# Control.net
KiCad netlist of a schematic drawn in Altium Designer
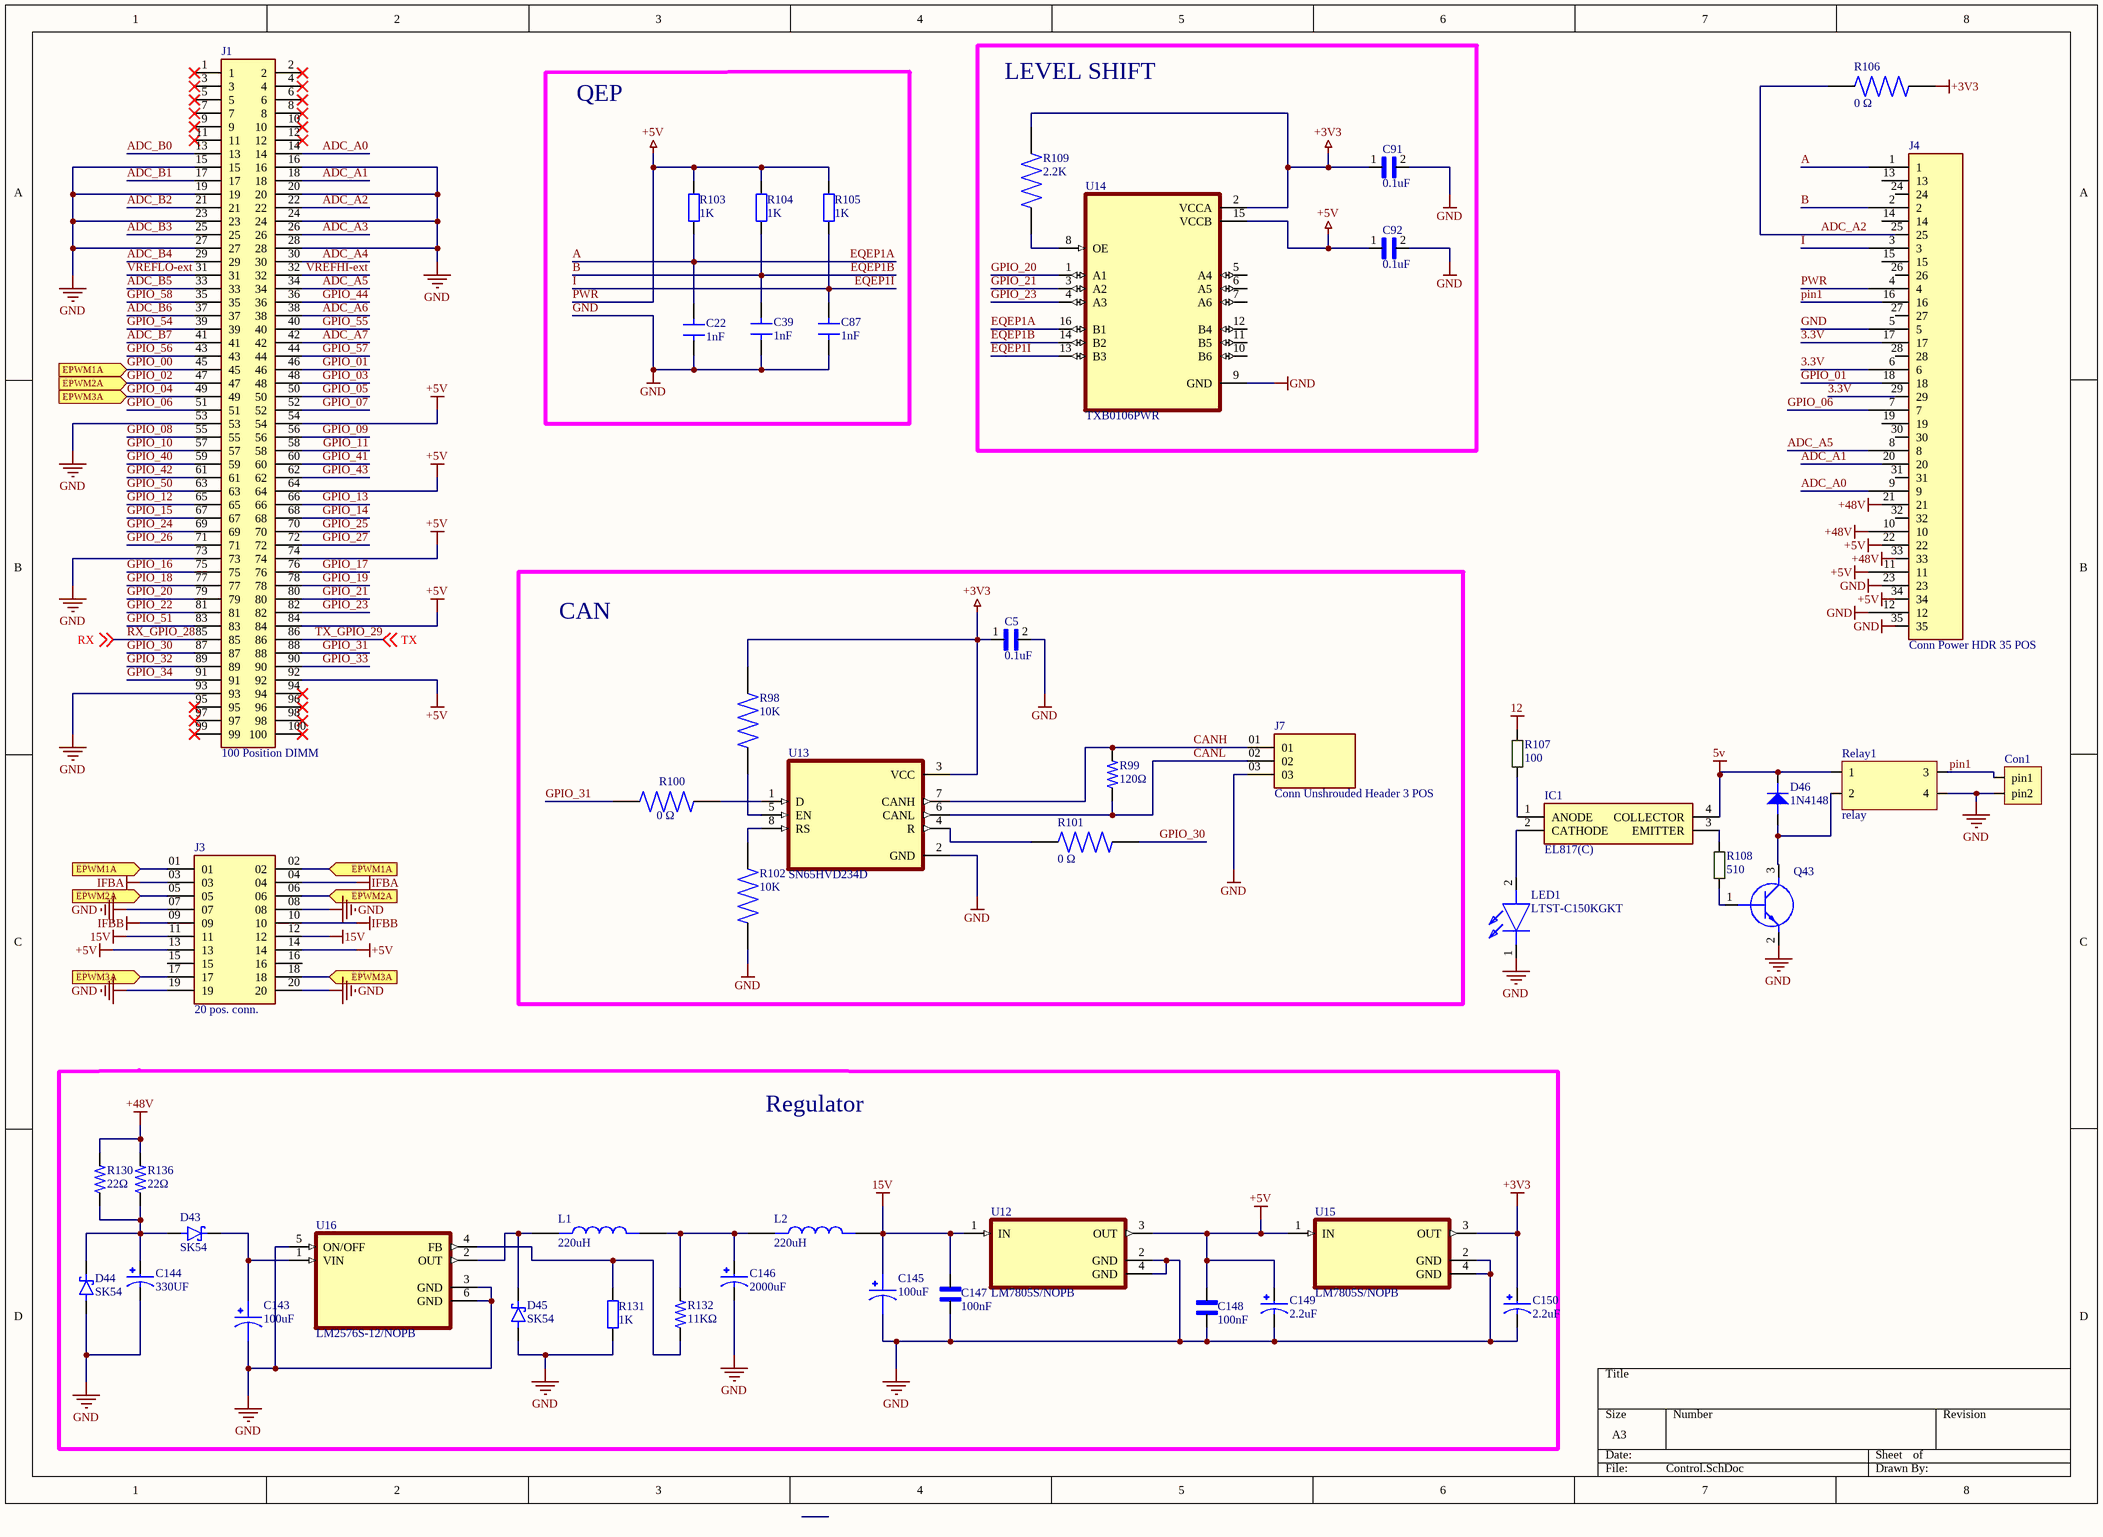
[diagram p0: Control.SchDoc]

(export (version "E")
  (design (tool "Eeschema 10.0.6"))
  (components
    (comp (ref "C5")
      (value "0.1uF")
      (footprint "CAPC2012X88N")
      (description "Cap Ceramic 0.1uF 35V X7R 10% SMD 0805 125Â°C Paper T/R")
      (fields (field (name "MP") "C0805C104K6RACTU") (field (name "MF") "KEMET"))
      (libsource (lib "PROJE") (part "CAP 0.1uF SMD 0805"))
    )
    (comp (ref "C22")
      (value "1nF")
      (footprint "CAP 1206_3216 - 1.8MM")
      (libsource (lib "PROJE") (part "CAP 1nF 1206"))
    )
    (comp (ref "C39")
      (value "1nF")
      (footprint "CAP 1206_3216 - 1.8MM")
      (libsource (lib "PROJE") (part "CAP 1nF 1206"))
    )
    (comp (ref "C87")
      (value "1nF")
      (footprint "CAP 1206_3216 - 1.8MM")
      (libsource (lib "PROJE") (part "CAP 1nF 1206"))
    )
    (comp (ref "C91")
      (value "0.1uF")
      (footprint "CAPC2012X88N")
      (description "Cap Ceramic 0.1uF 35V X7R 10% SMD 0805 125Â°C Paper T/R")
      (fields (field (name "MP") "C0805C104K6RACTU") (field (name "MF") "KEMET"))
      (libsource (lib "PROJE") (part "CAP 0.1uF SMD 0805"))
    )
    (comp (ref "C92")
      (value "0.1uF")
      (footprint "CAPC2012X88N")
      (description "Cap Ceramic 0.1uF 35V X7R 10% SMD 0805 125Â°C Paper T/R")
      (fields (field (name "MP") "C0805C104K6RACTU") (field (name "MF") "KEMET"))
      (libsource (lib "PROJE") (part "CAP 0.1uF SMD 0805"))
    )
    (comp (ref "C143")
      (value "100uF")
      (footprint "CapSmdElc")
      (libsource (lib "PROJE") (part "100 uF Electr Cap"))
    )
    (comp (ref "C144")
      (value "330UF")
      (footprint "CAP_EEETC1C331V")
      (description "CAP ALUM 330UF 20% 16V SMD")
      (fields (field (name "MP") "EEE-TC1C331V") (field (name "MF") "Panasonic Electronic Components"))
      (libsource (lib "PROJE") (part "CAP 330UF SMD"))
    )
    (comp (ref "C145")
      (value "100uF")
      (footprint "CapSmdElc")
      (libsource (lib "PROJE") (part "100 uF Electr Cap"))
    )
    (comp (ref "C146")
      (value "2000uF")
      (footprint "CAPPRD500W60D1000H1600")
      (description "CAP ALUM 2000UF 20% 6.3V RADIAL - Electrolytic")
      (fields (field (name "MP") "EEUFS0J202") (field (name "MF") "Panasonic"))
      (libsource (lib "PROJE") (part "2000uF"))
    )
    (comp (ref "C147")
      (value "100nF")
      (footprint "C-0805W")
      (fields
        (field (name "MF") "Wurth Electronics Inc")
        (field (name "MP") "885012207098")
        (field (name "BUYPART") "https://www.snapeda.com/parts/885012207098/Wurth%20Electronics%20Inc/view-part/4217223/?ref=eda")
      )
      (libsource (lib "PROJE") (part "CAP 100nF 50V SMT 0805"))
    )
    (comp (ref "C148")
      (value "100nF")
      (footprint "C-0805W")
      (fields
        (field (name "MF") "Wurth Electronics Inc")
        (field (name "MP") "885012207098")
        (field (name "BUYPART") "https://www.snapeda.com/parts/885012207098/Wurth%20Electronics%20Inc/view-part/4217223/?ref=eda")
      )
      (libsource (lib "PROJE") (part "CAP 100nF 50V SMT 0805"))
    )
    (comp (ref "C149")
      (value "2.2uF")
      (footprint "CapSmdElc")
      (description "Electrolytic Capacitor")
      (libsource (lib "PROJE") (part "CAP 2.2uF"))
    )
    (comp (ref "C150")
      (value "2.2uF")
      (footprint "CapSmdElc")
      (description "Electrolytic Capacitor")
      (libsource (lib "PROJE") (part "CAP 2.2uF"))
    )
    (comp (ref "Con1")
      (value "2pinConnector")
      (footprint "2pinCon")
      (description "CON.T.B.2.54MM 2P 180C MALE IVORY CONNFLY")
      (fields (field (name "ÖZDISAN PART NUMBER") "DS1070-2MVV6") (field (name "MANUFACTURER") "CONNFLY"))
      (libsource (lib "Mobile Charger") (part "2pinConnector"))
    )
    (comp (ref "D43")
      (value "SK54")
      (footprint "DIOM7959X265N")
      (description "Diode Schottky 40V 5A Surface Mount DO-214AA (SMB)")
      (fields (field (name "MP") "MBRS320T3G") (field (name "MF") "ON Semiconductor"))
      (libsource (lib "PROJE") (part "SK54"))
    )
    (comp (ref "D44")
      (value "SK54")
      (footprint "DIOM7959X265N")
      (description "Diode Schottky 40V 5A Surface Mount DO-214AA (SMB)")
      (fields (field (name "MP") "MBRS320T3G") (field (name "MF") "ON Semiconductor"))
      (libsource (lib "PROJE") (part "SK54"))
    )
    (comp (ref "D45")
      (value "SK54")
      (footprint "DIOM7959X265N")
      (description "Diode Schottky 40V 5A Surface Mount DO-214AA (SMB)")
      (fields (field (name "MP") "MBRS320T3G") (field (name "MF") "ON Semiconductor"))
      (libsource (lib "PROJE") (part "SK54"))
    )
    (comp (ref "D46")
      (value "1N4148")
      (footprint "SOD-123")
      (description "DIODE FAST SWITCHING Single 150mA 75V SMT SOD323")
      (fields (field (name "ÖZDISAN PART NUMBER") "1N4148WS-HT") (field (name "MANUFACTURER") "HOTTECH"))
      (libsource (lib "Mobile Charger") (part "1N4148"))
    )
    (comp (ref "IC1")
      (value "EL817(C)")
      (footprint "DIP762W60P254L458H480Q4N")
      (description "IC-817 OPTOC.TRANS.OUTPUT DIP4")
      (fields (field (name "ÖZDISAN PART NUMBER") "PC817B=PC817X2NSZW") (field (name "MANUFACTURER") "SHARP"))
      (libsource (lib "Mobile Charger") (part "EL817(C)"))
    )
    (comp (ref "J1")
      (value "100 Position DIMM")
      (footprint "TE_5390213-1")
      (description "100 Position DIMM DRAM Socket Through Hole")
      (fields (field (name "MP") "5390213-1") (field (name "MF") "TE Connectivity"))
      (libsource (lib "PROJE") (part "100 Position DIMM"))
    )
    (comp (ref "J3")
      (value "20 pos. conn.")
      (footprint "SAMTEC_SSQ-110-X-X-D")
      (description "SSQ - Samtec 2.54mm Square Tail Dual Row Socket Strip 8.5mm Profile - Fast Stock")
      (fields (field (name "MF") "Samtec") (field (name "MP") "SSQ-110-23-G-D"))
      (libsource (lib "PROJE") (part "20 pos. conn."))
    )
    (comp (ref "J4")
      (value "Conn Power HDR 35 POS")
      (footprint "TE_776230-2")
      (description "Conn Power HDR 35 POS 4mm Solder ST Thru-Hole 35 Terminal 1 Port Automotive Loose")
      (fields (field (name "MP") "776230-2") (field (name "MF") "TE Connectivity"))
      (libsource (lib "PROJE") (part "Conn Power HDR 35 POS"))
    )
    (comp (ref "J7")
      (value "Conn Unshrouded Header 3 POS")
      (footprint "SAMTEC_TSW-103-17-S-S")
      (fields (field (name "MP") "TSW-103-17-S-S"))
      (libsource (lib "PROJE") (part "Conn Unshrouded Header 3 POS"))
    )
    (comp (ref "L1")
      (value "220uH")
      (footprint "IND_MDH12577C-101MA=P3")
      (description "Inductor Power Shielded Wirewound 220uH 20% 100KHz Ferrite 1.1A 0.325Ohm DCR 5049 Automotive T/R")
      (fields (field (name "MP") "MDH12577C-101MA=P3"))
      (libsource (lib "PROJE") (part "220uH Inductor SMD"))
    )
    (comp (ref "L2")
      (value "220uH")
      (footprint "IND_MDH12577C-101MA=P3")
      (description "Inductor Power Shielded Wirewound 220uH 20% 100KHz Ferrite 1.1A 0.325Ohm DCR 5049 Automotive T/R")
      (fields (field (name "MP") "MDH12577C-101MA=P3"))
      (libsource (lib "PROJE") (part "220uH Inductor SMD"))
    )
    (comp (ref "LED1")
      (value "LTST-C150KGKT")
      (footprint "L-1206")
      (description "LED SMD 1206 GREEN WATER CLEAR 18~71 mcd")
      (fields (field (name "MANUFACTURER") "LITEON"))
      (libsource (lib "Mobile Charger") (part "LTST-C150KGKT"))
    )
    (comp (ref "Q43")
      (value "BC817-40,235")
      (footprint "SamacSys:SOT95P230X110-3N")
      (description "TRANSISTOR DIS.500mA 45V NPN SOT23 GEN. SMT")
      (fields (field (name "MANUFACTURER") "NXP (PHILIPS)"))
      (libsource (lib "*") (part "BC817-40,235"))
    )
    (comp (ref "R98")
      (value "10K")
      (footprint "RESC2012X70N")
      (description "Precision Thick Film Surface Mnt Resistor 0805 10kOhm +/-0.5% 0.1W +/-50ppm/degC")
      (fields (field (name "MP") "ERJ6RBD1002V") (field (name "MF") "Panasonic"))
      (libsource (lib "PROJE") (part "RES 10K 0805"))
    )
    (comp (ref "R99")
      (value "120Ω")
      (footprint "RESC2012X65N")
      (description "RESISTOR, THICK FILM, 120R, 5%, 0805")
      (fields (field (name "MP") "CRGS0805J120R"))
      (libsource (lib "PROJE") (part "RES 120Ω 0805"))
    )
    (comp (ref "R100")
      (value "0 Ω")
      (footprint "RES 0.0 OHM 1206")
      (libsource (lib "PROJE") (part "RES 0.0 Ω 1206"))
    )
    (comp (ref "R101")
      (value "0 Ω")
      (footprint "RES 0.0 OHM 1206")
      (libsource (lib "PROJE") (part "RES 0.0 Ω 1206"))
    )
    (comp (ref "R102")
      (value "10K")
      (footprint "RESC2012X70N")
      (description "Precision Thick Film Surface Mnt Resistor 0805 10kOhm +/-0.5% 0.1W +/-50ppm/degC")
      (fields (field (name "MP") "ERJ6RBD1002V") (field (name "MF") "Panasonic"))
      (libsource (lib "PROJE") (part "RES 10K 0805"))
    )
    (comp (ref "R103")
      (value "RES SMD 1K OHM 1% 1/8W 0805")
      (footprint "RES_0805")
      (description "1 kOhms ±1% 0.125W, 1/8W Chip Resistor 0805 (2012 Metric) Moisture Resistant Thick Film")
      (fields (field (name "DEGER") "1K"))
      (libsource (lib "PROJE") (part "1K 0805"))
    )
    (comp (ref "R104")
      (value "RES SMD 1K OHM 1% 1/8W 0805")
      (footprint "RES_0805")
      (description "1 kOhms ±1% 0.125W, 1/8W Chip Resistor 0805 (2012 Metric) Moisture Resistant Thick Film")
      (fields (field (name "DEGER") "1K"))
      (libsource (lib "PROJE") (part "1K 0805"))
    )
    (comp (ref "R105")
      (value "RES SMD 1K OHM 1% 1/8W 0805")
      (footprint "RES_0805")
      (description "1 kOhms ±1% 0.125W, 1/8W Chip Resistor 0805 (2012 Metric) Moisture Resistant Thick Film")
      (fields (field (name "DEGER") "1K"))
      (libsource (lib "PROJE") (part "1K 0805"))
    )
    (comp (ref "R106")
      (value "0 Ω")
      (footprint "RES 0.0 OHM 1206")
      (libsource (lib "PROJE") (part "RES 0.0 Ω 1206"))
    )
    (comp (ref "R107")
      (value "100")
      (footprint "R-1206")
      (description "RES.(3216) 1206 100 Ohms 5% 1/4W 100PPM")
      (fields (field (name "ÖZDISAN PART NUMBER") "RC3216J101CS") (field (name "MANUFACTURER") "SAMSUNG"))
      (libsource (lib "Mobile Charger") (part "R-1206"))
    )
    (comp (ref "R108")
      (value "510")
      (footprint "R-1206")
      (description "RES.(3216) 1206 510 Ohms 1% 1/4W-S 100PPM")
      (fields (field (name "ÖZDISAN PART NUMBER") "1206S4F5100T5E") (field (name "MANUFACTURER") "ROYALOHM"))
      (libsource (lib "Mobile Charger") (part "R-1206"))
    )
    (comp (ref "R109")
      (value "2.2K")
      (footprint "RESC3115X65N-2.2K-1206")
      (description "RES SMD 2.2K OHM 1% 1/4W 1206")
      (fields (field (name "MP") "CRG1206F2K2/10"))
      (libsource (lib "PROJE") (part "RES 2.2K 1206"))
    )
    (comp (ref "R130") (value "22Ω") (footprint "R-2512R") (libsource (lib "PROJE") (part "RES 22Ω 2512")))
    (comp (ref "R131")
      (value "RES SMD 1K OHM 1% 1/8W 0805")
      (footprint "RES_0805")
      (description "1 kOhms ±1% 0.125W, 1/8W Chip Resistor 0805 (2012 Metric) Moisture Resistant Thick Film")
      (fields (field (name "DEGER") "1K"))
      (libsource (lib "PROJE") (part "1K 0805"))
    )
    (comp (ref "R132")
      (value "11KΩ")
      (footprint "RESC2012X50N")
      (description "THICK FILM RESISTOR, 11KOHM, 125mW, 5%")
      (fields (field (name "MP") "CRCW080511K0JNEA"))
      (libsource (lib "PROJE") (part "RES 11KΩ SMD"))
    )
    (comp (ref "R136") (value "22Ω") (footprint "R-2512R") (libsource (lib "PROJE") (part "RES 22Ω 2512")))
    (comp (ref "Relay1")
      (value "relay")
      (footprint "Relay")
      (description "RELAY 3A 5VDC 1a PANASONIC")
      (fields (field (name "ÖZDISAN PART NUMBER") "ALJ105W") (field (name "MANUFACTURER") "PANASONIC COMP."))
      (libsource (lib "Mobile Charger") (part "relay"))
    )
    (comp (ref "U12")
      (value "LM7805S/NOPB")
      (footprint "TO254P1524X483-4N")
      (description "1.5-A, 30-V, linear voltage regulator 3-DDPAK/TO-263 0 to 125")
      (fields (field (name "MF") "Texas Instruments"))
      (libsource (lib "PROJE") (part "LM7805S/NOPB"))
    )
    (comp (ref "U13")
      (value "SN65HVD234D")
      (footprint "SOIC127P599X175-8N")
      (description "3.3 V CAN Transceiver with Sleep Mode 8-SOIC -40 to 125")
      (fields (field (name "MF") "Texas Instruments"))
      (libsource (lib "PROJE") (part "SN65HVD234D"))
    )
    (comp (ref "U14")
      (value "TXB0106PWR")
      (footprint "SOP65P640X120-16N")
      (fields
        (field (name "MF") "Texas Instruments")
        (field (name "BUYPART") "https://www.snapeda.com/parts/TXB0106PWR/Texas%20Instruments/view-part/134340/?ref=eda")
      )
      (libsource (lib "PROJE") (part "TXB0106PWR"))
    )
    (comp (ref "U15")
      (value "LM7805S/NOPB")
      (footprint "TO254P1524X483-4N")
      (description "1.5-A, 30-V, linear voltage regulator 3-DDPAK/TO-263 0 to 125")
      (fields (field (name "MF") "Texas Instruments"))
      (libsource (lib "PROJE") (part "LM7805S/NOPB"))
    )
    (comp (ref "U16")
      (value "LM2576S-12/NOPB")
      (footprint "VREG_TPS79625KTTR")
      (description "SIMPLE SWITCHER&reg; 40V, 3A Low Component Count Step-Down Regulator 5-DDPAK/TO-263 -40 to 125")
      (fields
        (field (name "MF") "Texas Instruments")
        (field (name "BUYPART") "https://www.snapeda.com/parts/LM2576S-12/NOPB/Texas%20Instruments/view-part/470772/?ref=eda")
      )
      (libsource (lib "PROJE") (part "LM2576S-12/NOPB"))
    )
  )
  (nets
    (net (code "1") (name "+3V3") (class "Default")
      (node (ref "C150") (pin "1") (pinfunction "1_1") (pintype "passive"))
      (node (ref "C5") (pin "1") (pinfunction "1_1") (pintype "passive"))
      (node (ref "C91") (pin "1") (pinfunction "1_1") (pintype "passive"))
      (node (ref "R106") (pin "1") (pinfunction "1_1") (pintype "passive"))
      (node (ref "R109") (pin "2") (pinfunction "2_2") (pintype "passive"))
      (node (ref "R98") (pin "2") (pinfunction "2_2") (pintype "passive"))
      (node (ref "U13") (pin "3") (pinfunction "VCC_3") (pintype "power_in"))
      (node (ref "U14") (pin "2") (pinfunction "VCCA_2") (pintype "power_in"))
      (node (ref "U15") (pin "3") (pinfunction "OUT_3") (pintype "output"))
    )
    (net (code "2") (name "+5V") (class "Default")
      (node (ref "C148") (pin "2") (pinfunction "2_2") (pintype "passive"))
      (node (ref "C149") (pin "1") (pinfunction "1_1") (pintype "passive"))
      (node (ref "C92") (pin "1") (pinfunction "1_1") (pintype "passive"))
      (node (ref "J1") (pin "54") (pinfunction "54_54") (pintype "passive"))
      (node (ref "J1") (pin "64") (pinfunction "64_64") (pintype "passive"))
      (node (ref "J1") (pin "74") (pinfunction "74_74") (pintype "passive"))
      (node (ref "J1") (pin "84") (pinfunction "84_84") (pintype "passive"))
      (node (ref "J1") (pin "92") (pinfunction "92_92") (pintype "passive"))
      (node (ref "J3") (pin "13") (pinfunction "13_13") (pintype "passive"))
      (node (ref "J3") (pin "14") (pinfunction "14_14") (pintype "passive"))
      (node (ref "J4") (pin "11") (pinfunction "11_11") (pintype "passive"))
      (node (ref "J4") (pin "22") (pinfunction "22_22") (pintype "passive"))
      (node (ref "J4") (pin "34") (pinfunction "34_34") (pintype "passive"))
      (node (ref "J4") (pin "4") (pinfunction "4_4") (pintype "passive"))
      (node (ref "R103") (pin "2") (pinfunction "2_2") (pintype "passive"))
      (node (ref "R104") (pin "2") (pinfunction "2_2") (pintype "passive"))
      (node (ref "R105") (pin "2") (pinfunction "2_2") (pintype "passive"))
      (node (ref "U12") (pin "3") (pinfunction "OUT_3") (pintype "output"))
      (node (ref "U14") (pin "15") (pinfunction "VCCB_15") (pintype "power_in"))
      (node (ref "U15") (pin "1") (pinfunction "IN_1") (pintype "input"))
    )
    (net (code "3") (name "+48V") (class "Default")
      (node (ref "J4") (pin "10") (pinfunction "10_10") (pintype "passive"))
      (node (ref "J4") (pin "21") (pinfunction "21_21") (pintype "passive"))
      (node (ref "J4") (pin "33") (pinfunction "33_33") (pintype "passive"))
      (node (ref "R130") (pin "2") (pinfunction "2_2") (pintype "passive"))
      (node (ref "R136") (pin "2") (pinfunction "2_2") (pintype "passive"))
    )
    (net (code "4") (name "/3.3V") (class "Default")
      (node (ref "J4") (pin "17") (pinfunction "17_17") (pintype "passive"))
      (node (ref "J4") (pin "29") (pinfunction "29_29") (pintype "passive"))
      (node (ref "J4") (pin "6") (pinfunction "6_6") (pintype "passive"))
    )
    (net (code "5") (name "/A") (class "Default")
      (node (ref "C22") (pin "2") (pinfunction "2_2") (pintype "passive"))
      (node (ref "J4") (pin "1") (pinfunction "1_1") (pintype "passive"))
      (node (ref "R103") (pin "1") (pinfunction "1_1") (pintype "passive"))
      (node (ref "U14") (pin "16") (pinfunction "B1_16") (pintype "bidirectional"))
    )
    (net (code "6") (name "/ADC_A0") (class "Default")
      (node (ref "J1") (pin "14") (pinfunction "14_14") (pintype "passive"))
      (node (ref "J4") (pin "9") (pinfunction "9_9") (pintype "passive"))
    )
    (net (code "7") (name "/ADC_A1") (class "Default")
      (node (ref "J1") (pin "18") (pinfunction "18_18") (pintype "passive"))
      (node (ref "J4") (pin "20") (pinfunction "20_20") (pintype "passive"))
    )
    (net (code "8") (name "/ADC_A2") (class "Default")
      (node (ref "J1") (pin "22") (pinfunction "22_22") (pintype "passive"))
      (node (ref "J4") (pin "25") (pinfunction "25_25") (pintype "passive"))
      (node (ref "R106") (pin "2") (pinfunction "2_2") (pintype "passive"))
    )
    (net (code "9") (name "/ADC_A3") (class "Default")
      (node (ref "J1") (pin "26") (pinfunction "26_26") (pintype "passive"))
    )
    (net (code "10") (name "/ADC_A4") (class "Default")
      (node (ref "J1") (pin "30") (pinfunction "30_30") (pintype "passive"))
    )
    (net (code "11") (name "/ADC_A5") (class "Default")
      (node (ref "J1") (pin "34") (pinfunction "34_34") (pintype "passive"))
      (node (ref "J4") (pin "8") (pinfunction "8_8") (pintype "passive"))
    )
    (net (code "12") (name "/ADC_A6") (class "Default")
      (node (ref "J1") (pin "38") (pinfunction "38_38") (pintype "passive"))
    )
    (net (code "13") (name "/ADC_A7") (class "Default")
      (node (ref "J1") (pin "42") (pinfunction "42_42") (pintype "passive"))
    )
    (net (code "14") (name "/ADC_B0") (class "Default")
      (node (ref "J1") (pin "13") (pinfunction "13_13") (pintype "passive"))
    )
    (net (code "15") (name "/ADC_B1") (class "Default")
      (node (ref "J1") (pin "17") (pinfunction "17_17") (pintype "passive"))
    )
    (net (code "16") (name "/ADC_B2") (class "Default")
      (node (ref "J1") (pin "21") (pinfunction "21_21") (pintype "passive"))
    )
    (net (code "17") (name "/ADC_B3") (class "Default")
      (node (ref "J1") (pin "25") (pinfunction "25_25") (pintype "passive"))
    )
    (net (code "18") (name "/ADC_B4") (class "Default")
      (node (ref "J1") (pin "29") (pinfunction "29_29") (pintype "passive"))
    )
    (net (code "19") (name "/ADC_B5") (class "Default")
      (node (ref "J1") (pin "33") (pinfunction "33_33") (pintype "passive"))
    )
    (net (code "20") (name "/ADC_B6") (class "Default")
      (node (ref "J1") (pin "37") (pinfunction "37_37") (pintype "passive"))
    )
    (net (code "21") (name "/ADC_B7") (class "Default")
      (node (ref "J1") (pin "41") (pinfunction "41_41") (pintype "passive"))
    )
    (net (code "22") (name "/B") (class "Default")
      (node (ref "C39") (pin "2") (pinfunction "2_2") (pintype "passive"))
      (node (ref "J4") (pin "2") (pinfunction "2_2") (pintype "passive"))
      (node (ref "R104") (pin "1") (pinfunction "1_1") (pintype "passive"))
      (node (ref "U14") (pin "14") (pinfunction "B2_14") (pintype "bidirectional"))
    )
    (net (code "23") (name "/CANH") (class "Default")
      (node (ref "J7") (pin "01") (pinfunction "01_01") (pintype "passive"))
      (node (ref "R99") (pin "2") (pinfunction "2_2") (pintype "passive"))
      (node (ref "U13") (pin "7") (pinfunction "CANH_7") (pintype "output"))
    )
    (net (code "24") (name "/CANL") (class "Default")
      (node (ref "J7") (pin "02") (pinfunction "02_02") (pintype "passive"))
      (node (ref "R99") (pin "1") (pinfunction "1_1") (pintype "passive"))
      (node (ref "U13") (pin "6") (pinfunction "CANL_6") (pintype "output"))
    )
    (net (code "25") (name "/EQEP1I") (class "Default")
      (node (ref "C87") (pin "2") (pinfunction "2_2") (pintype "passive"))
      (node (ref "J4") (pin "3") (pinfunction "3_3") (pintype "passive"))
      (node (ref "R105") (pin "1") (pinfunction "1_1") (pintype "passive"))
      (node (ref "U14") (pin "13") (pinfunction "B3_13") (pintype "bidirectional"))
    )
    (net (code "26") (name "/GPIO_00") (class "Default")
      (node (ref "J1") (pin "45") (pinfunction "45_45") (pintype "passive"))
      (node (ref "J3") (pin "01") (pinfunction "01_01") (pintype "passive"))
      (node (ref "J3") (pin "02") (pinfunction "02_02") (pintype "passive"))
    )
    (net (code "27") (name "/GPIO_01") (class "Default")
      (node (ref "J1") (pin "46") (pinfunction "46_46") (pintype "passive"))
      (node (ref "J4") (pin "18") (pinfunction "18_18") (pintype "passive"))
    )
    (net (code "28") (name "/GPIO_02") (class "Default")
      (node (ref "J1") (pin "47") (pinfunction "47_47") (pintype "passive"))
      (node (ref "J3") (pin "05") (pinfunction "05_05") (pintype "passive"))
      (node (ref "J3") (pin "06") (pinfunction "06_06") (pintype "passive"))
    )
    (net (code "29") (name "/GPIO_03") (class "Default")
      (node (ref "J1") (pin "48") (pinfunction "48_48") (pintype "passive"))
    )
    (net (code "30") (name "/GPIO_04") (class "Default")
      (node (ref "J1") (pin "49") (pinfunction "49_49") (pintype "passive"))
      (node (ref "J3") (pin "17") (pinfunction "17_17") (pintype "passive"))
      (node (ref "J3") (pin "18") (pinfunction "18_18") (pintype "passive"))
    )
    (net (code "31") (name "/GPIO_05") (class "Default")
      (node (ref "J1") (pin "50") (pinfunction "50_50") (pintype "passive"))
    )
    (net (code "32") (name "/GPIO_06") (class "Default")
      (node (ref "J1") (pin "51") (pinfunction "51_51") (pintype "passive"))
      (node (ref "J4") (pin "7") (pinfunction "7_7") (pintype "passive"))
    )
    (net (code "33") (name "/GPIO_07") (class "Default")
      (node (ref "J1") (pin "52") (pinfunction "52_52") (pintype "passive"))
    )
    (net (code "34") (name "/GPIO_08") (class "Default")
      (node (ref "J1") (pin "55") (pinfunction "55_55") (pintype "passive"))
    )
    (net (code "35") (name "/GPIO_09") (class "Default")
      (node (ref "J1") (pin "56") (pinfunction "56_56") (pintype "passive"))
    )
    (net (code "36") (name "/GPIO_10") (class "Default")
      (node (ref "J1") (pin "57") (pinfunction "57_57") (pintype "passive"))
    )
    (net (code "37") (name "/GPIO_11") (class "Default")
      (node (ref "J1") (pin "58") (pinfunction "58_58") (pintype "passive"))
    )
    (net (code "38") (name "/GPIO_12") (class "Default")
      (node (ref "J1") (pin "65") (pinfunction "65_65") (pintype "passive"))
    )
    (net (code "39") (name "/GPIO_13") (class "Default")
      (node (ref "J1") (pin "66") (pinfunction "66_66") (pintype "passive"))
    )
    (net (code "40") (name "/GPIO_14") (class "Default")
      (node (ref "J1") (pin "68") (pinfunction "68_68") (pintype "passive"))
    )
    (net (code "41") (name "/GPIO_15") (class "Default")
      (node (ref "J1") (pin "67") (pinfunction "67_67") (pintype "passive"))
    )
    (net (code "42") (name "/GPIO_16") (class "Default")
      (node (ref "J1") (pin "75") (pinfunction "75_75") (pintype "passive"))
    )
    (net (code "43") (name "/GPIO_17") (class "Default")
      (node (ref "J1") (pin "76") (pinfunction "76_76") (pintype "passive"))
    )
    (net (code "44") (name "/GPIO_18") (class "Default")
      (node (ref "J1") (pin "77") (pinfunction "77_77") (pintype "passive"))
    )
    (net (code "45") (name "/GPIO_19") (class "Default")
      (node (ref "J1") (pin "78") (pinfunction "78_78") (pintype "passive"))
    )
    (net (code "46") (name "/GPIO_20") (class "Default")
      (node (ref "J1") (pin "79") (pinfunction "79_79") (pintype "passive"))
      (node (ref "U14") (pin "1") (pinfunction "A1_1") (pintype "bidirectional"))
    )
    (net (code "47") (name "/GPIO_21") (class "Default")
      (node (ref "J1") (pin "80") (pinfunction "80_80") (pintype "passive"))
      (node (ref "U14") (pin "3") (pinfunction "A2_3") (pintype "bidirectional"))
    )
    (net (code "48") (name "/GPIO_22") (class "Default")
      (node (ref "J1") (pin "81") (pinfunction "81_81") (pintype "passive"))
    )
    (net (code "49") (name "/GPIO_23") (class "Default")
      (node (ref "J1") (pin "82") (pinfunction "82_82") (pintype "passive"))
      (node (ref "U14") (pin "4") (pinfunction "A3_4") (pintype "bidirectional"))
    )
    (net (code "50") (name "/GPIO_24") (class "Default")
      (node (ref "J1") (pin "69") (pinfunction "69_69") (pintype "passive"))
    )
    (net (code "51") (name "/GPIO_25") (class "Default")
      (node (ref "J1") (pin "70") (pinfunction "70_70") (pintype "passive"))
    )
    (net (code "52") (name "/GPIO_26") (class "Default")
      (node (ref "J1") (pin "71") (pinfunction "71_71") (pintype "passive"))
    )
    (net (code "53") (name "/GPIO_27") (class "Default")
      (node (ref "J1") (pin "72") (pinfunction "72_72") (pintype "passive"))
    )
    (net (code "54") (name "/GPIO_30") (class "Default")
      (node (ref "J1") (pin "87") (pinfunction "87_87") (pintype "passive"))
      (node (ref "R101") (pin "1") (pinfunction "1_1") (pintype "passive"))
    )
    (net (code "55") (name "/GPIO_31") (class "Default")
      (node (ref "J1") (pin "88") (pinfunction "88_88") (pintype "passive"))
      (node (ref "R100") (pin "1") (pinfunction "1_1") (pintype "passive"))
    )
    (net (code "56") (name "/GPIO_32") (class "Default")
      (node (ref "J1") (pin "89") (pinfunction "89_89") (pintype "passive"))
    )
    (net (code "57") (name "/GPIO_33") (class "Default")
      (node (ref "J1") (pin "90") (pinfunction "90_90") (pintype "passive"))
    )
    (net (code "58") (name "/GPIO_34") (class "Default")
      (node (ref "J1") (pin "91") (pinfunction "91_91") (pintype "passive"))
    )
    (net (code "59") (name "/GPIO_40") (class "Default")
      (node (ref "J1") (pin "59") (pinfunction "59_59") (pintype "passive"))
    )
    (net (code "60") (name "/GPIO_41") (class "Default")
      (node (ref "J1") (pin "60") (pinfunction "60_60") (pintype "passive"))
    )
    (net (code "61") (name "/GPIO_42") (class "Default")
      (node (ref "J1") (pin "61") (pinfunction "61_61") (pintype "passive"))
    )
    (net (code "62") (name "/GPIO_43") (class "Default")
      (node (ref "J1") (pin "62") (pinfunction "62_62") (pintype "passive"))
    )
    (net (code "63") (name "/GPIO_44") (class "Default")
      (node (ref "J1") (pin "36") (pinfunction "36_36") (pintype "passive"))
    )
    (net (code "64") (name "/GPIO_50") (class "Default")
      (node (ref "J1") (pin "63") (pinfunction "63_63") (pintype "passive"))
    )
    (net (code "65") (name "/GPIO_51") (class "Default")
      (node (ref "J1") (pin "83") (pinfunction "83_83") (pintype "passive"))
    )
    (net (code "66") (name "/GPIO_54") (class "Default")
      (node (ref "J1") (pin "39") (pinfunction "39_39") (pintype "passive"))
    )
    (net (code "67") (name "/GPIO_55") (class "Default")
      (node (ref "J1") (pin "40") (pinfunction "40_40") (pintype "passive"))
    )
    (net (code "68") (name "/GPIO_56") (class "Default")
      (node (ref "J1") (pin "43") (pinfunction "43_43") (pintype "passive"))
    )
    (net (code "69") (name "/GPIO_57") (class "Default")
      (node (ref "J1") (pin "44") (pinfunction "44_44") (pintype "passive"))
    )
    (net (code "70") (name "/GPIO_58") (class "Default")
      (node (ref "J1") (pin "35") (pinfunction "35_35") (pintype "passive"))
    )
    (net (code "71") (name "/VREFHI-ext") (class "Default")
      (node (ref "J1") (pin "32") (pinfunction "32_32") (pintype "passive"))
    )
    (net (code "72") (name "/VREFLO-ext") (class "Default")
      (node (ref "J1") (pin "31") (pinfunction "31_31") (pintype "passive"))
    )
    (net (code "73") (name "/pin1") (class "Default")
      (node (ref "Con1") (pin "1") (pinfunction "pin1_1") (pintype "passive"))
      (node (ref "J4") (pin "16") (pinfunction "16_16") (pintype "passive"))
      (node (ref "Relay1") (pin "3") (pinfunction "3_3") (pintype "passive"))
    )
    (net (code "74") (name "5v") (class "Default")
      (node (ref "D46") (pin "k") (pinfunction "k_k") (pintype "passive"))
      (node (ref "IC1") (pin "4") (pinfunction "COLLECTOR_4") (pintype "passive"))
      (node (ref "Relay1") (pin "1") (pinfunction "1_1") (pintype "passive"))
    )
    (net (code "75") (name "12") (class "Default")
      (node (ref "R107") (pin "2") (pinfunction "2_2") (pintype "passive"))
    )
    (net (code "76") (name "15V") (class "Default")
      (node (ref "C145") (pin "1") (pinfunction "1_1") (pintype "passive"))
      (node (ref "C147") (pin "2") (pinfunction "2_2") (pintype "passive"))
      (node (ref "J3") (pin "11") (pinfunction "11_11") (pintype "passive"))
      (node (ref "J3") (pin "12") (pinfunction "12_12") (pintype "passive"))
      (node (ref "L2") (pin "2") (pinfunction "2_2") (pintype "passive"))
      (node (ref "U12") (pin "1") (pinfunction "IN_1") (pintype "input"))
    )
    (net (code "77") (name "GND") (class "Default")
      (node (ref "C143") (pin "2") (pinfunction "2_2") (pintype "passive"))
      (node (ref "C144") (pin "2") (pinfunction "2_2") (pintype "passive"))
      (node (ref "C145") (pin "2") (pinfunction "2_2") (pintype "passive"))
      (node (ref "C146") (pin "N") (pinfunction "N_N") (pintype "passive"))
      (node (ref "C147") (pin "1") (pinfunction "1_1") (pintype "passive"))
      (node (ref "C148") (pin "1") (pinfunction "1_1") (pintype "passive"))
      (node (ref "C149") (pin "2") (pinfunction "2_2") (pintype "passive"))
      (node (ref "C150") (pin "2") (pinfunction "2_2") (pintype "passive"))
      (node (ref "C22") (pin "1") (pinfunction "1_1") (pintype "passive"))
      (node (ref "C39") (pin "1") (pinfunction "1_1") (pintype "passive"))
      (node (ref "C5") (pin "2") (pinfunction "2_2") (pintype "passive"))
      (node (ref "C87") (pin "1") (pinfunction "1_1") (pintype "passive"))
      (node (ref "C91") (pin "2") (pinfunction "2_2") (pintype "passive"))
      (node (ref "C92") (pin "2") (pinfunction "2_2") (pintype "passive"))
      (node (ref "Con1") (pin "2") (pinfunction "pin2_2") (pintype "passive"))
      (node (ref "D44") (pin "A") (pinfunction "A_A") (pintype "passive"))
      (node (ref "D45") (pin "A") (pinfunction "A_A") (pintype "passive"))
      (node (ref "J1") (pin "15") (pinfunction "15_15") (pintype "passive"))
      (node (ref "J1") (pin "16") (pinfunction "16_16") (pintype "passive"))
      (node (ref "J1") (pin "19") (pinfunction "19_19") (pintype "passive"))
      (node (ref "J1") (pin "20") (pinfunction "20_20") (pintype "passive"))
      (node (ref "J1") (pin "23") (pinfunction "23_23") (pintype "passive"))
      (node (ref "J1") (pin "24") (pinfunction "24_24") (pintype "passive"))
      (node (ref "J1") (pin "27") (pinfunction "27_27") (pintype "passive"))
      (node (ref "J1") (pin "28") (pinfunction "28_28") (pintype "passive"))
      (node (ref "J1") (pin "53") (pinfunction "53_53") (pintype "passive"))
      (node (ref "J1") (pin "73") (pinfunction "73_73") (pintype "passive"))
      (node (ref "J1") (pin "93") (pinfunction "93_93") (pintype "passive"))
      (node (ref "J3") (pin "07") (pinfunction "07_07") (pintype "passive"))
      (node (ref "J3") (pin "08") (pinfunction "08_08") (pintype "passive"))
      (node (ref "J3") (pin "19") (pinfunction "19_19") (pintype "passive"))
      (node (ref "J3") (pin "20") (pinfunction "20_20") (pintype "passive"))
      (node (ref "J4") (pin "12") (pinfunction "12_12") (pintype "passive"))
      (node (ref "J4") (pin "23") (pinfunction "23_23") (pintype "passive"))
      (node (ref "J4") (pin "35") (pinfunction "35_35") (pintype "passive"))
      (node (ref "J4") (pin "5") (pinfunction "5_5") (pintype "passive"))
      (node (ref "J7") (pin "03") (pinfunction "03_03") (pintype "passive"))
      (node (ref "LED1") (pin "1") (pinfunction "K_1") (pintype "passive"))
      (node (ref "Q43") (pin "2") (pinfunction "E_2") (pintype "passive"))
      (node (ref "R102") (pin "1") (pinfunction "1_1") (pintype "passive"))
      (node (ref "R131") (pin "1") (pinfunction "1_1") (pintype "passive"))
      (node (ref "Relay1") (pin "4") (pinfunction "4_4") (pintype "passive"))
      (node (ref "U12") (pin "2") (pinfunction "GND_2") (pintype "power_in"))
      (node (ref "U12") (pin "4") (pinfunction "GND_4") (pintype "power_in"))
      (node (ref "U13") (pin "2") (pinfunction "GND_2") (pintype "power_in"))
      (node (ref "U14") (pin "9") (pinfunction "GND_9") (pintype "power_in"))
      (node (ref "U15") (pin "2") (pinfunction "GND_2") (pintype "power_in"))
      (node (ref "U15") (pin "4") (pinfunction "GND_4") (pintype "power_in"))
      (node (ref "U16") (pin "3") (pinfunction "GND_3") (pintype "power_in"))
      (node (ref "U16") (pin "5") (pinfunction "ON/OFF_5") (pintype "input"))
      (node (ref "U16") (pin "6") (pinfunction "GND_6") (pintype "power_in"))
    )
    (net (code "78") (name "IFBA") (class "Default")
      (node (ref "J3") (pin "03") (pinfunction "03_03") (pintype "passive"))
      (node (ref "J3") (pin "04") (pinfunction "04_04") (pintype "passive"))
    )
    (net (code "79") (name "IFBB") (class "Default")
      (node (ref "J3") (pin "09") (pinfunction "09_09") (pintype "passive"))
      (node (ref "J3") (pin "10") (pinfunction "10_10") (pintype "passive"))
    )
    (net (code "80") (name "Net-(C146-PadP)") (class "Default")
      (node (ref "C146") (pin "P") (pinfunction "P_P") (pintype "passive"))
      (node (ref "L1") (pin "2") (pinfunction "2_2") (pintype "passive"))
      (node (ref "L2") (pin "1") (pinfunction "1_1") (pintype "passive"))
      (node (ref "R132") (pin "2") (pinfunction "2_2") (pintype "passive"))
    )
    (net (code "81") (name "Net-(D43-K)") (class "Default")
      (node (ref "C143") (pin "1") (pinfunction "1_1") (pintype "passive"))
      (node (ref "D43") (pin "C") (pinfunction "K_C") (pintype "passive"))
      (node (ref "U16") (pin "1") (pinfunction "VIN_1") (pintype "input"))
    )
    (net (code "82") (name "Net-(D44-K)") (class "Default")
      (node (ref "C144") (pin "1") (pinfunction "1_1") (pintype "passive"))
      (node (ref "D43") (pin "A") (pinfunction "A_A") (pintype "passive"))
      (node (ref "D44") (pin "C") (pinfunction "K_C") (pintype "passive"))
      (node (ref "R130") (pin "1") (pinfunction "1_1") (pintype "passive"))
      (node (ref "R136") (pin "1") (pinfunction "1_1") (pintype "passive"))
    )
    (net (code "83") (name "Net-(D45-K)") (class "Default")
      (node (ref "D45") (pin "C") (pinfunction "K_C") (pintype "passive"))
      (node (ref "L1") (pin "1") (pinfunction "1_1") (pintype "passive"))
      (node (ref "U16") (pin "2") (pinfunction "OUT_2") (pintype "output"))
    )
    (net (code "84") (name "Net-(IC1-ANODE)") (class "Default")
      (node (ref "IC1") (pin "1") (pinfunction "ANODE_1") (pintype "passive"))
      (node (ref "R107") (pin "1") (pinfunction "1_1") (pintype "passive"))
    )
    (net (code "85") (name "Net-(IC1-CATHODE)") (class "Default")
      (node (ref "IC1") (pin "2") (pinfunction "CATHODE_2") (pintype "passive"))
      (node (ref "LED1") (pin "2") (pinfunction "A_2") (pintype "passive"))
    )
    (net (code "86") (name "Net-(IC1-EMITTER)") (class "Default")
      (node (ref "IC1") (pin "3") (pinfunction "EMITTER_3") (pintype "passive"))
      (node (ref "R108") (pin "2") (pinfunction "2_2") (pintype "passive"))
    )
    (net (code "87") (name "Net-(Q43-B)") (class "Default")
      (node (ref "Q43") (pin "1") (pinfunction "B_1") (pintype "passive"))
      (node (ref "R108") (pin "1") (pinfunction "1_1") (pintype "passive"))
    )
    (net (code "88") (name "Net-(Q43-C)") (class "Default")
      (node (ref "D46") (pin "a") (pinfunction "a_a") (pintype "passive"))
      (node (ref "Q43") (pin "3") (pinfunction "C_3") (pintype "passive"))
      (node (ref "Relay1") (pin "2") (pinfunction "2_2") (pintype "passive"))
    )
    (net (code "89") (name "Net-(U13-D)") (class "Default")
      (node (ref "R100") (pin "2") (pinfunction "2_2") (pintype "passive"))
      (node (ref "U13") (pin "1") (pinfunction "D_1") (pintype "input"))
    )
    (net (code "90") (name "Net-(U13-EN)") (class "Default")
      (node (ref "R98") (pin "1") (pinfunction "1_1") (pintype "passive"))
      (node (ref "U13") (pin "5") (pinfunction "EN_5") (pintype "input"))
    )
    (net (code "91") (name "Net-(U13-R)") (class "Default")
      (node (ref "R101") (pin "2") (pinfunction "2_2") (pintype "passive"))
      (node (ref "U13") (pin "4") (pinfunction "R_4") (pintype "output"))
    )
    (net (code "92") (name "Net-(U13-RS)") (class "Default")
      (node (ref "R102") (pin "2") (pinfunction "2_2") (pintype "passive"))
      (node (ref "U13") (pin "8") (pinfunction "RS_8") (pintype "input"))
    )
    (net (code "93") (name "Net-(U14-OE)") (class "Default")
      (node (ref "R109") (pin "1") (pinfunction "1_1") (pintype "passive"))
      (node (ref "U14") (pin "8") (pinfunction "OE_8") (pintype "input"))
    )
    (net (code "94") (name "Net-(U16-FB)") (class "Default")
      (node (ref "R131") (pin "2") (pinfunction "2_2") (pintype "passive"))
      (node (ref "R132") (pin "1") (pinfunction "1_1") (pintype "passive"))
      (node (ref "U16") (pin "4") (pinfunction "FB_4") (pintype "output"))
    )
    (net (code "95") (name "RX") (class "Default")
      (node (ref "J1") (pin "85") (pinfunction "85_85") (pintype "passive"))
    )
    (net (code "96") (name "TX") (class "Default")
      (node (ref "J1") (pin "86") (pinfunction "86_86") (pintype "passive"))
    )
    (net (code "97") (name "unconnected-(J1-Pad1)") (class "Default")
      (node (ref "J1") (pin "1") (pinfunction "1_1") (pintype "passive+no_connect"))
    )
    (net (code "98") (name "unconnected-(J1-Pad2)") (class "Default")
      (node (ref "J1") (pin "2") (pinfunction "2_2") (pintype "passive+no_connect"))
    )
    (net (code "99") (name "unconnected-(J1-Pad3)") (class "Default")
      (node (ref "J1") (pin "3") (pinfunction "3_3") (pintype "passive+no_connect"))
    )
    (net (code "100") (name "unconnected-(J1-Pad4)") (class "Default")
      (node (ref "J1") (pin "4") (pinfunction "4_4") (pintype "passive+no_connect"))
    )
    (net (code "101") (name "unconnected-(J1-Pad5)") (class "Default")
      (node (ref "J1") (pin "5") (pinfunction "5_5") (pintype "passive+no_connect"))
    )
    (net (code "102") (name "unconnected-(J1-Pad6)") (class "Default")
      (node (ref "J1") (pin "6") (pinfunction "6_6") (pintype "passive+no_connect"))
    )
    (net (code "103") (name "unconnected-(J1-Pad7)") (class "Default")
      (node (ref "J1") (pin "7") (pinfunction "7_7") (pintype "passive+no_connect"))
    )
    (net (code "104") (name "unconnected-(J1-Pad8)") (class "Default")
      (node (ref "J1") (pin "8") (pinfunction "8_8") (pintype "passive+no_connect"))
    )
    (net (code "105") (name "unconnected-(J1-Pad9)") (class "Default")
      (node (ref "J1") (pin "9") (pinfunction "9_9") (pintype "passive+no_connect"))
    )
    (net (code "106") (name "unconnected-(J1-Pad10)") (class "Default")
      (node (ref "J1") (pin "10") (pinfunction "10_10") (pintype "passive+no_connect"))
    )
    (net (code "107") (name "unconnected-(J1-Pad11)") (class "Default")
      (node (ref "J1") (pin "11") (pinfunction "11_11") (pintype "passive+no_connect"))
    )
    (net (code "108") (name "unconnected-(J1-Pad12)") (class "Default")
      (node (ref "J1") (pin "12") (pinfunction "12_12") (pintype "passive+no_connect"))
    )
    (net (code "109") (name "unconnected-(J1-Pad94)") (class "Default")
      (node (ref "J1") (pin "94") (pinfunction "94_94") (pintype "passive+no_connect"))
    )
    (net (code "110") (name "unconnected-(J1-Pad95)") (class "Default")
      (node (ref "J1") (pin "95") (pinfunction "95_95") (pintype "passive+no_connect"))
    )
    (net (code "111") (name "unconnected-(J1-Pad96)") (class "Default")
      (node (ref "J1") (pin "96") (pinfunction "96_96") (pintype "passive+no_connect"))
    )
    (net (code "112") (name "unconnected-(J1-Pad97)") (class "Default")
      (node (ref "J1") (pin "97") (pinfunction "97_97") (pintype "passive+no_connect"))
    )
    (net (code "113") (name "unconnected-(J1-Pad98)") (class "Default")
      (node (ref "J1") (pin "98") (pinfunction "98_98") (pintype "passive+no_connect"))
    )
    (net (code "114") (name "unconnected-(J1-Pad99)") (class "Default")
      (node (ref "J1") (pin "99") (pinfunction "99_99") (pintype "passive+no_connect"))
    )
    (net (code "115") (name "unconnected-(J1-Pad100)") (class "Default")
      (node (ref "J1") (pin "100") (pinfunction "100_100") (pintype "passive+no_connect"))
    )
    (net (code "116") (name "unconnected-(J3-Pad15)") (class "Default")
      (node (ref "J3") (pin "15") (pinfunction "15_15") (pintype "passive"))
    )
    (net (code "117") (name "unconnected-(J3-Pad16)") (class "Default")
      (node (ref "J3") (pin "16") (pinfunction "16_16") (pintype "passive"))
    )
    (net (code "118") (name "unconnected-(J4-Pad13)") (class "Default")
      (node (ref "J4") (pin "13") (pinfunction "13_13") (pintype "passive"))
    )
    (net (code "119") (name "unconnected-(J4-Pad14)") (class "Default")
      (node (ref "J4") (pin "14") (pinfunction "14_14") (pintype "passive"))
    )
    (net (code "120") (name "unconnected-(J4-Pad15)") (class "Default")
      (node (ref "J4") (pin "15") (pinfunction "15_15") (pintype "passive"))
    )
    (net (code "121") (name "unconnected-(J4-Pad19)") (class "Default")
      (node (ref "J4") (pin "19") (pinfunction "19_19") (pintype "passive"))
    )
    (net (code "122") (name "unconnected-(J4-Pad24)") (class "Default")
      (node (ref "J4") (pin "24") (pinfunction "24_24") (pintype "passive"))
    )
    (net (code "123") (name "unconnected-(J4-Pad26)") (class "Default")
      (node (ref "J4") (pin "26") (pinfunction "26_26") (pintype "passive"))
    )
    (net (code "124") (name "unconnected-(J4-Pad27)") (class "Default")
      (node (ref "J4") (pin "27") (pinfunction "27_27") (pintype "passive"))
    )
    (net (code "125") (name "unconnected-(J4-Pad28)") (class "Default")
      (node (ref "J4") (pin "28") (pinfunction "28_28") (pintype "passive"))
    )
    (net (code "126") (name "unconnected-(J4-Pad30)") (class "Default")
      (node (ref "J4") (pin "30") (pinfunction "30_30") (pintype "passive"))
    )
    (net (code "127") (name "unconnected-(J4-Pad31)") (class "Default")
      (node (ref "J4") (pin "31") (pinfunction "31_31") (pintype "passive"))
    )
    (net (code "128") (name "unconnected-(J4-Pad32)") (class "Default")
      (node (ref "J4") (pin "32") (pinfunction "32_32") (pintype "passive"))
    )
    (net (code "129") (name "unconnected-(U14-A4-Pad5)") (class "Default")
      (node (ref "U14") (pin "5") (pinfunction "A4_5") (pintype "bidirectional"))
    )
    (net (code "130") (name "unconnected-(U14-A5-Pad6)") (class "Default")
      (node (ref "U14") (pin "6") (pinfunction "A5_6") (pintype "bidirectional"))
    )
    (net (code "131") (name "unconnected-(U14-A6-Pad7)") (class "Default")
      (node (ref "U14") (pin "7") (pinfunction "A6_7") (pintype "bidirectional"))
    )
    (net (code "132") (name "unconnected-(U14-B4-Pad12)") (class "Default")
      (node (ref "U14") (pin "12") (pinfunction "B4_12") (pintype "bidirectional"))
    )
    (net (code "133") (name "unconnected-(U14-B5-Pad11)") (class "Default")
      (node (ref "U14") (pin "11") (pinfunction "B5_11") (pintype "bidirectional"))
    )
    (net (code "134") (name "unconnected-(U14-B6-Pad10)") (class "Default")
      (node (ref "U14") (pin "10") (pinfunction "B6_10") (pintype "bidirectional"))
    )
  )
)
